# SNES_RGBAmp.net
KiCad netlist of a schematic drawn in EAGLE
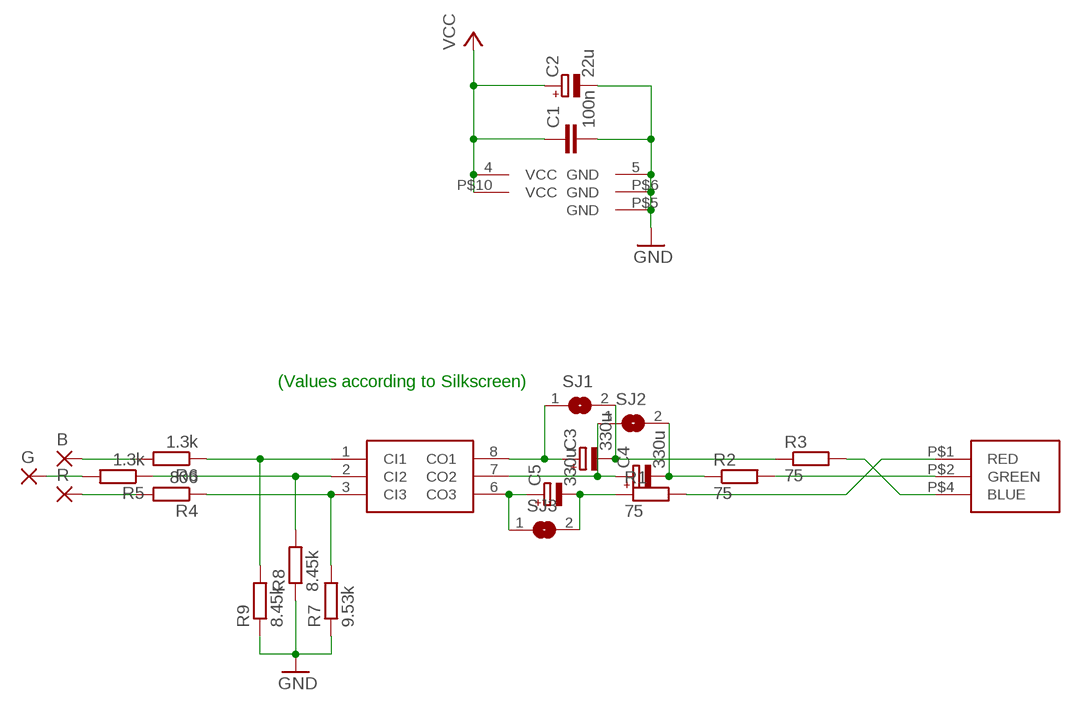
[diagram p0: schematic, sheet 1]

(export (version "E")
  (design (tool "Eeschema 10.0.6"))
  (components
    (comp (ref "B")
      (value "SMD2")
      (footprint "eagle-import:SMD1,27-2,54")
      (libsource (lib "eagle-import") (part "SMD2"))
    )
    (comp (ref "C1")
      (value "100n")
      (footprint "eagle-import:Z0805")
      (libsource (lib "eagle-import") (part "C0805"))
    )
    (comp (ref "C2")
      (value "22u")
      (footprint "eagle-import:SMC_C")
      (libsource (lib "eagle-import") (part "CPOL-EUSMCC"))
    )
    (comp (ref "C3")
      (value "330u")
      (footprint "eagle-import:SMC_D")
      (libsource (lib "eagle-import") (part "CPOL-EUSMCD"))
    )
    (comp (ref "C4")
      (value "330u")
      (footprint "eagle-import:SMC_D")
      (libsource (lib "eagle-import") (part "CPOL-EUSMCD"))
    )
    (comp (ref "C5")
      (value "330u")
      (footprint "eagle-import:SMC_D")
      (libsource (lib "eagle-import") (part "CPOL-EUSMCD"))
    )
    (comp (ref "G")
      (value "SMD2")
      (footprint "eagle-import:SMD1,27-2,54")
      (libsource (lib "eagle-import") (part "SMD2"))
    )
    (comp (ref "R")
      (value "SMD2")
      (footprint "eagle-import:SMD1,27-2,54")
      (libsource (lib "eagle-import") (part "SMD2"))
    )
    (comp (ref "R1")
      (value "75")
      (footprint "eagle-import:Z0805")
      (libsource (lib "eagle-import") (part "R0805"))
    )
    (comp (ref "R2")
      (value "75")
      (footprint "eagle-import:Z0805")
      (libsource (lib "eagle-import") (part "R0805"))
    )
    (comp (ref "R3")
      (value "75")
      (footprint "eagle-import:Z0805")
      (libsource (lib "eagle-import") (part "R0805"))
    )
    (comp (ref "R4")
      (value "806")
      (footprint "eagle-import:Z0805")
      (libsource (lib "eagle-import") (part "R0805"))
    )
    (comp (ref "R5")
      (value "1.3k")
      (footprint "eagle-import:Z0805")
      (libsource (lib "eagle-import") (part "R0805"))
    )
    (comp (ref "R6")
      (value "1.3k")
      (footprint "eagle-import:Z0805")
      (libsource (lib "eagle-import") (part "R0805"))
    )
    (comp (ref "R7")
      (value "9.53k")
      (footprint "eagle-import:Z0805")
      (libsource (lib "eagle-import") (part "R0805"))
    )
    (comp (ref "R8")
      (value "8.45k")
      (footprint "eagle-import:Z0805")
      (libsource (lib "eagle-import") (part "R0805"))
    )
    (comp (ref "R9")
      (value "8.45k")
      (footprint "eagle-import:Z0805")
      (libsource (lib "eagle-import") (part "R0805"))
    )
    (comp (ref "SJ1") (value "SJ") (footprint "eagle-import:SJ") (libsource (lib "eagle-import") (part "SJ")))
    (comp (ref "SJ2") (value "SJ") (footprint "eagle-import:SJ") (libsource (lib "eagle-import") (part "SJ")))
    (comp (ref "SJ3") (value "SJ") (footprint "eagle-import:SJ") (libsource (lib "eagle-import") (part "SJ")))
    (comp (ref "U$1")
      (value "THS7314")
      (footprint "eagle-import:THS7314")
      (libsource (lib "eagle-import") (part "THS7314"))
    )
    (comp (ref "U$2")
      (value "SNES_MULTIAV_RGB_ONLY")
      (footprint "eagle-import:SNES_MULTIAV_RGB_ONLY")
      (libsource (lib "eagle-import") (part "SNES_MULTIAV_RGB_ONLY"))
    )
  )
  (nets
    (net (code "1") (name "GND") (class "Default")
      (node (ref "C1") (pin "2") (pinfunction "2_2") (pintype "passive"))
      (node (ref "C2") (pin "-") (pinfunction "-_-") (pintype "passive"))
      (node (ref "R7") (pin "1") (pinfunction "1_1") (pintype "passive"))
      (node (ref "R8") (pin "1") (pinfunction "1_1") (pintype "passive"))
      (node (ref "R9") (pin "1") (pinfunction "1_1") (pintype "passive"))
      (node (ref "U$1") (pin "5") (pinfunction "GND_5") (pintype "bidirectional"))
      (node (ref "U$2") (pin "P$5") (pinfunction "GND_P$5") (pintype "bidirectional"))
      (node (ref "U$2") (pin "P$6") (pinfunction "GND_P$6") (pintype "bidirectional"))
    )
    (net (code "2") (name "Net-(B-P)") (class "Default")
      (node (ref "B") (pin "1") (pinfunction "P_1") (pintype "passive"))
      (node (ref "R6") (pin "2") (pinfunction "2_2") (pintype "passive"))
    )
    (net (code "3") (name "Net-(C3-Pad-)") (class "Default")
      (node (ref "C3") (pin "-") (pinfunction "-_-") (pintype "passive"))
      (node (ref "R3") (pin "1") (pinfunction "1_1") (pintype "passive"))
      (node (ref "SJ1") (pin "2") (pinfunction "2_2") (pintype "passive"))
    )
    (net (code "4") (name "Net-(C4-Pad-)") (class "Default")
      (node (ref "C4") (pin "-") (pinfunction "-_-") (pintype "passive"))
      (node (ref "R2") (pin "1") (pinfunction "1_1") (pintype "passive"))
      (node (ref "SJ2") (pin "2") (pinfunction "2_2") (pintype "passive"))
    )
    (net (code "5") (name "Net-(C5-Pad-)") (class "Default")
      (node (ref "C5") (pin "-") (pinfunction "-_-") (pintype "passive"))
      (node (ref "R1") (pin "1") (pinfunction "1_1") (pintype "passive"))
      (node (ref "SJ3") (pin "2") (pinfunction "2_2") (pintype "passive"))
    )
    (net (code "6") (name "Net-(G-P)") (class "Default")
      (node (ref "G") (pin "1") (pinfunction "P_1") (pintype "passive"))
      (node (ref "R5") (pin "2") (pinfunction "2_2") (pintype "passive"))
    )
    (net (code "7") (name "Net-(R-P)") (class "Default")
      (node (ref "R") (pin "1") (pinfunction "P_1") (pintype "passive"))
      (node (ref "R4") (pin "2") (pinfunction "2_2") (pintype "passive"))
    )
    (net (code "8") (name "Net-(U$1A-CI1)") (class "Default")
      (node (ref "R6") (pin "1") (pinfunction "1_1") (pintype "passive"))
      (node (ref "R9") (pin "2") (pinfunction "2_2") (pintype "passive"))
      (node (ref "U$1") (pin "1") (pinfunction "CI1_1") (pintype "bidirectional"))
    )
    (net (code "9") (name "Net-(U$1A-CI2)") (class "Default")
      (node (ref "R5") (pin "1") (pinfunction "1_1") (pintype "passive"))
      (node (ref "R8") (pin "2") (pinfunction "2_2") (pintype "passive"))
      (node (ref "U$1") (pin "2") (pinfunction "CI2_2") (pintype "bidirectional"))
    )
    (net (code "10") (name "Net-(U$1A-CI3)") (class "Default")
      (node (ref "R4") (pin "1") (pinfunction "1_1") (pintype "passive"))
      (node (ref "R7") (pin "2") (pinfunction "2_2") (pintype "passive"))
      (node (ref "U$1") (pin "3") (pinfunction "CI3_3") (pintype "bidirectional"))
    )
    (net (code "11") (name "Net-(U$1A-CO1)") (class "Default")
      (node (ref "C3") (pin "+") (pinfunction "+_+") (pintype "passive"))
      (node (ref "SJ1") (pin "1") (pinfunction "1_1") (pintype "passive"))
      (node (ref "U$1") (pin "8") (pinfunction "CO1_8") (pintype "bidirectional"))
    )
    (net (code "12") (name "Net-(U$1A-CO2)") (class "Default")
      (node (ref "C4") (pin "+") (pinfunction "+_+") (pintype "passive"))
      (node (ref "SJ2") (pin "1") (pinfunction "1_1") (pintype "passive"))
      (node (ref "U$1") (pin "7") (pinfunction "CO2_7") (pintype "bidirectional"))
    )
    (net (code "13") (name "Net-(U$1A-CO3)") (class "Default")
      (node (ref "C5") (pin "+") (pinfunction "+_+") (pintype "passive"))
      (node (ref "SJ3") (pin "1") (pinfunction "1_1") (pintype "passive"))
      (node (ref "U$1") (pin "6") (pinfunction "CO3_6") (pintype "bidirectional"))
    )
    (net (code "14") (name "Net-(U$2C-BLUE)") (class "Default")
      (node (ref "R3") (pin "2") (pinfunction "2_2") (pintype "passive"))
      (node (ref "U$2") (pin "P$4") (pinfunction "BLUE_P$4") (pintype "bidirectional"))
    )
    (net (code "15") (name "Net-(U$2C-GREEN)") (class "Default")
      (node (ref "R2") (pin "2") (pinfunction "2_2") (pintype "passive"))
      (node (ref "U$2") (pin "P$2") (pinfunction "GREEN_P$2") (pintype "bidirectional"))
    )
    (net (code "16") (name "Net-(U$2C-RED)") (class "Default")
      (node (ref "R1") (pin "2") (pinfunction "2_2") (pintype "passive"))
      (node (ref "U$2") (pin "P$1") (pinfunction "RED_P$1") (pintype "bidirectional"))
    )
    (net (code "17") (name "VCC") (class "Default")
      (node (ref "C1") (pin "1") (pinfunction "1_1") (pintype "passive"))
      (node (ref "C2") (pin "+") (pinfunction "+_+") (pintype "passive"))
      (node (ref "U$1") (pin "4") (pinfunction "VCC_4") (pintype "bidirectional"))
      (node (ref "U$2") (pin "P$10") (pinfunction "VCC_P$10") (pintype "bidirectional"))
    )
  )
)
